# Power.net
KiCad netlist of a schematic drawn in Altium Designer
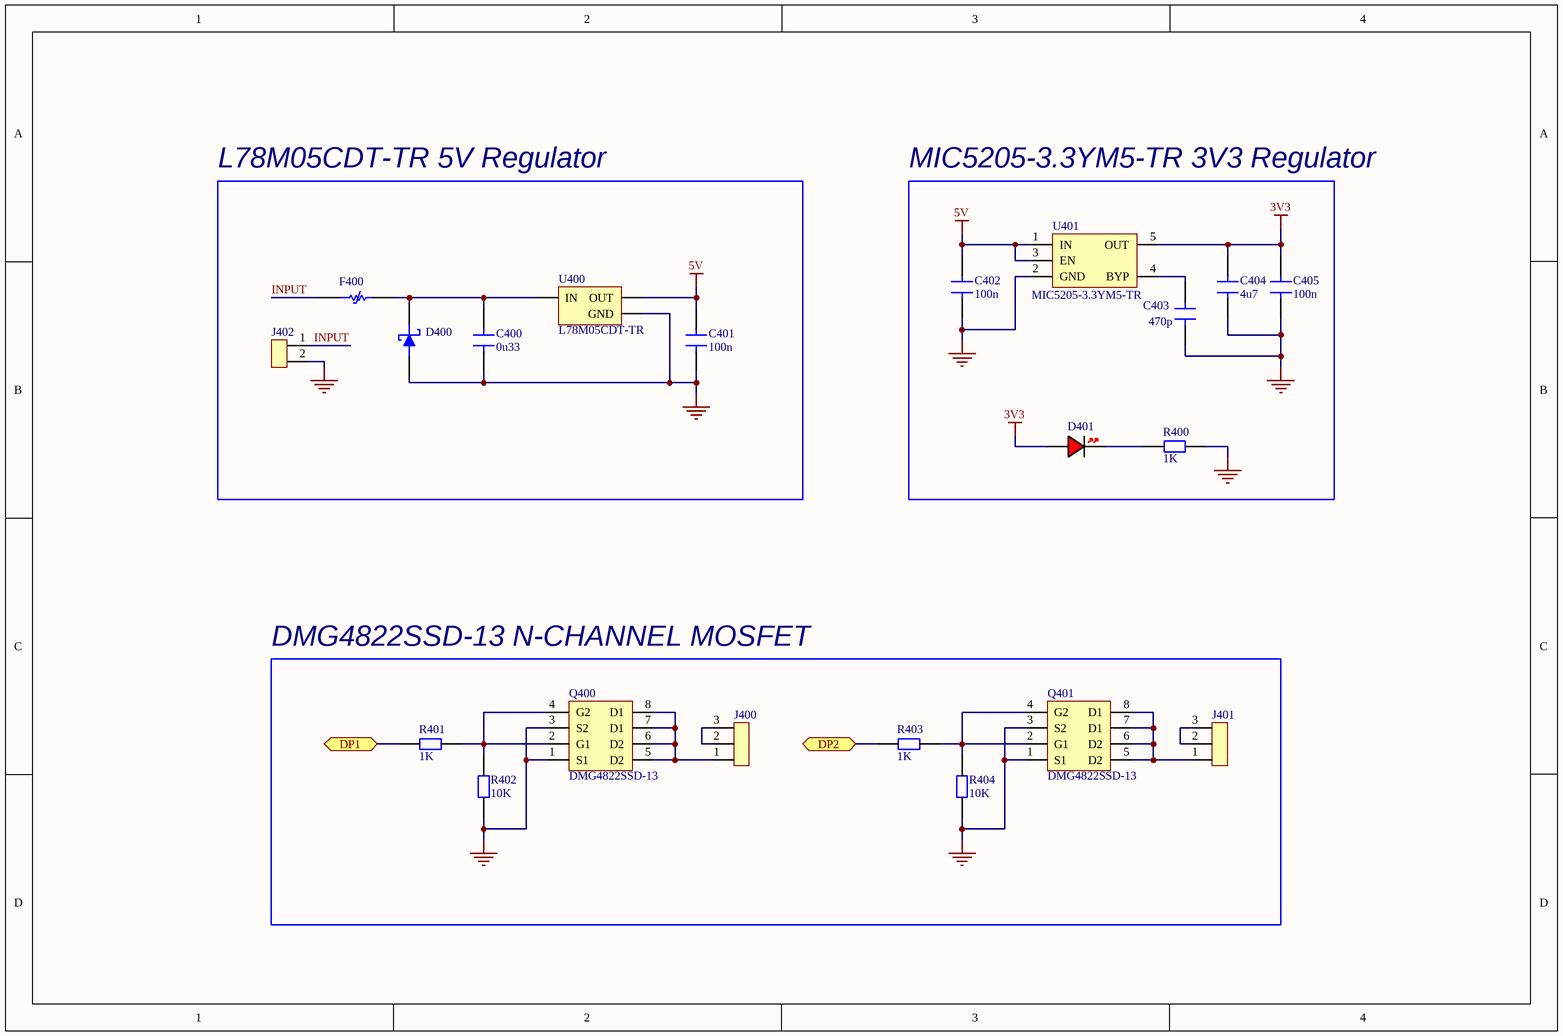
[diagram p0: Power.SchDoc]

(export (version "E")
  (design (tool "Eeschema 10.0.6"))
  (components
    (comp (ref "C400")
      (value "0u33")
      (footprint "CAP 0805")
      (description "Capacitor SMD 0805 50V")
      (libsource (lib "Schlib") (part "CAP 0805 50V"))
    )
    (comp (ref "C401")
      (value "100n")
      (footprint "CAP 0805")
      (description "Capacitor SMD 0805 50V")
      (libsource (lib "Schlib") (part "CAP 0805 50V"))
    )
    (comp (ref "C402")
      (value "100n")
      (footprint "CAP 0805")
      (description "Capacitor SMD 0805 50V")
      (libsource (lib "Schlib") (part "CAP 0805 50V"))
    )
    (comp (ref "C403")
      (value "470p")
      (footprint "CAP 0805")
      (description "Capacitor SMD 0805 50V")
      (libsource (lib "Schlib") (part "CAP 0805 50V"))
    )
    (comp (ref "C404")
      (value "4u7")
      (footprint "CAP 0805")
      (description "Capacitor SMD 0805 50V")
      (libsource (lib "Schlib") (part "CAP 0805 50V"))
    )
    (comp (ref "C405")
      (value "100n")
      (footprint "CAP 0805")
      (description "Capacitor SMD 0805 50V")
      (libsource (lib "Schlib") (part "CAP 0805 50V"))
    )
    (comp (ref "D400")
      (value "SMBJ12CA-13-F")
      (footprint "SMBJ12CA-13-F")
      (description "TVS DIODE 12VWM 19.9VC SMB")
      (fields (field (name "MANUFACTURER") "Diodes"))
      (libsource (lib "Schlib") (part "SMBJ12CA-13-F"))
    )
    (comp (ref "D401")
      (value "LED 0805 RED")
      (footprint "LED 0805 RED")
      (description "LED 0805 RED SMD")
      (libsource (lib "Schlib") (part "LED 0805 RED"))
    )
    (comp (ref "F400")
      (value "0ZCG0075FF2C")
      (footprint "0ZCG0075FF2C")
      (fields (field (name "MANUFACTURER") "Bel"))
      (libsource (lib "Schlib") (part "0ZCG0075FF2C"))
    )
    (comp (ref "J400")
      (value "KF301 3P Terminal")
      (footprint "KF301 3P")
      (description "3 Pin Screw Terminal Block 5mm")
      (libsource (lib "Schlib") (part "KF301 3P Terminal"))
    )
    (comp (ref "J401")
      (value "KF301 3P Terminal")
      (footprint "KF301 3P")
      (description "3 Pin Screw Terminal Block 5mm")
      (libsource (lib "Schlib") (part "KF301 3P Terminal"))
    )
    (comp (ref "J402")
      (value "KF301 2P Terminal")
      (footprint "KF301 2P")
      (description "2 Pin Screw Terminal Block 5mm")
      (libsource (lib "Schlib") (part "KF301 2P Terminal"))
    )
    (comp (ref "Q400")
      (value "DMG4822SSD-13")
      (footprint "DMG4822SSD-13")
      (description "Dual N-Channel 30 V 1.42 W 10.5 nC Enhancement Mode Mosfet - SOIC-8")
      (fields (field (name "MANUFACTURER") "Diodes"))
      (libsource (lib "Schlib") (part "DMG4822SSD-13"))
    )
    (comp (ref "Q401")
      (value "DMG4822SSD-13")
      (footprint "DMG4822SSD-13")
      (description "Dual N-Channel 30 V 1.42 W 10.5 nC Enhancement Mode Mosfet - SOIC-8")
      (fields (field (name "MANUFACTURER") "Diodes"))
      (libsource (lib "Schlib") (part "DMG4822SSD-13"))
    )
    (comp (ref "R400")
      (value "1K")
      (footprint "RES 0603")
      (description "Resistor SMD 0603")
      (libsource (lib "Schlib") (part "RES 0603"))
    )
    (comp (ref "R401")
      (value "1K")
      (footprint "RES 0603")
      (description "Resistor SMD 0603")
      (libsource (lib "Schlib") (part "RES 0603"))
    )
    (comp (ref "R402")
      (value "10K")
      (footprint "RES 0603")
      (description "Resistor SMD 0603")
      (libsource (lib "Schlib") (part "RES 0603"))
    )
    (comp (ref "R403")
      (value "1K")
      (footprint "RES 0603")
      (description "Resistor SMD 0603")
      (libsource (lib "Schlib") (part "RES 0603"))
    )
    (comp (ref "R404")
      (value "10K")
      (footprint "RES 0603")
      (description "Resistor SMD 0603")
      (libsource (lib "Schlib") (part "RES 0603"))
    )
    (comp (ref "U400")
      (value "L78M05CDT-TR")
      (footprint "L78M05CDT-TR")
      (description "IC REG LDO 5V 0.5A DPAK")
      (fields (field (name "MANUFACTURER") "STMicroelectronics") (field (name "TOLERANCE") "5%"))
      (libsource (lib "Schlib") (part "L78M05CDT-TR"))
    )
    (comp (ref "U401")
      (value "MIC5205-3.3YM5-TR")
      (footprint "MIC5205-3.3YM5-TR")
      (description "Linear Voltage Regulator IC Positive Fixed 1 Output 3.3V 150mA SOT-23-5")
      (fields (field (name "MANUFACTURER") "Microchip"))
      (libsource (lib "Schlib") (part "MIC5205-3.3YM5-TR"))
    )
  )
  (nets
    (net (code "1") (name "/DP1") (class "Default")
      (node (ref "R401") (pin "1") (pinfunction "1_1") (pintype "passive"))
    )
    (net (code "2") (name "/DP2") (class "Default")
      (node (ref "R403") (pin "1") (pinfunction "1_1") (pintype "passive"))
    )
    (net (code "3") (name "/INPUT") (class "Default")
      (node (ref "F400") (pin "1") (pintype "passive"))
      (node (ref "J402") (pin "1") (pinfunction "1_1") (pintype "passive"))
    )
    (net (code "4") (name "3V3") (class "Default")
      (node (ref "C404") (pin "2") (pinfunction "2_2") (pintype "passive"))
      (node (ref "C405") (pin "2") (pinfunction "2_2") (pintype "passive"))
      (node (ref "D401") (pin "A") (pinfunction "A_A") (pintype "passive"))
      (node (ref "U401") (pin "5") (pinfunction "OUT_5") (pintype "passive"))
    )
    (net (code "5") (name "5V") (class "Default")
      (node (ref "C401") (pin "2") (pinfunction "2_2") (pintype "passive"))
      (node (ref "C402") (pin "2") (pinfunction "2_2") (pintype "passive"))
      (node (ref "U400") (pin "3") (pinfunction "OUT_3") (pintype "passive"))
      (node (ref "U401") (pin "1") (pinfunction "IN_1") (pintype "passive"))
      (node (ref "U401") (pin "3") (pinfunction "EN_3") (pintype "passive"))
    )
    (net (code "6") (name "GND") (class "Default")
      (node (ref "C400") (pin "1") (pinfunction "1_1") (pintype "passive"))
      (node (ref "C401") (pin "1") (pinfunction "1_1") (pintype "passive"))
      (node (ref "C402") (pin "1") (pinfunction "1_1") (pintype "passive"))
      (node (ref "C403") (pin "1") (pinfunction "1_1") (pintype "passive"))
      (node (ref "C404") (pin "1") (pinfunction "1_1") (pintype "passive"))
      (node (ref "C405") (pin "1") (pinfunction "1_1") (pintype "passive"))
      (node (ref "D400") (pin "1") (pintype "passive"))
      (node (ref "J402") (pin "2") (pinfunction "2_2") (pintype "passive"))
      (node (ref "Q400") (pin "1") (pinfunction "S1_1") (pintype "passive"))
      (node (ref "Q400") (pin "3") (pinfunction "S2_3") (pintype "passive"))
      (node (ref "Q401") (pin "1") (pinfunction "S1_1") (pintype "passive"))
      (node (ref "Q401") (pin "3") (pinfunction "S2_3") (pintype "passive"))
      (node (ref "R400") (pin "2") (pinfunction "2_2") (pintype "passive"))
      (node (ref "R402") (pin "1") (pinfunction "1_1") (pintype "passive"))
      (node (ref "R404") (pin "1") (pinfunction "1_1") (pintype "passive"))
      (node (ref "U400") (pin "2") (pinfunction "GND_2") (pintype "passive"))
      (node (ref "U401") (pin "2") (pinfunction "GND_2") (pintype "passive"))
    )
    (net (code "7") (name "Net-(D401-PadK)") (class "Default")
      (node (ref "D401") (pin "K") (pinfunction "K_K") (pintype "passive"))
      (node (ref "R400") (pin "1") (pinfunction "1_1") (pintype "passive"))
    )
    (net (code "8") (name "Net-(J400-Pad1)") (class "Default")
      (node (ref "J400") (pin "1") (pinfunction "1_1") (pintype "passive"))
      (node (ref "Q400") (pin "5") (pinfunction "D2_5") (pintype "passive"))
      (node (ref "Q400") (pin "6") (pinfunction "D2_6") (pintype "passive"))
      (node (ref "Q400") (pin "7") (pinfunction "D1_7") (pintype "passive"))
      (node (ref "Q400") (pin "8") (pinfunction "D1_8") (pintype "passive"))
    )
    (net (code "9") (name "Net-(J400-Pad2)") (class "Default")
      (node (ref "J400") (pin "2") (pinfunction "2_2") (pintype "passive"))
      (node (ref "J400") (pin "3") (pinfunction "3_3") (pintype "passive"))
    )
    (net (code "10") (name "Net-(J401-Pad1)") (class "Default")
      (node (ref "J401") (pin "1") (pinfunction "1_1") (pintype "passive"))
      (node (ref "Q401") (pin "5") (pinfunction "D2_5") (pintype "passive"))
      (node (ref "Q401") (pin "6") (pinfunction "D2_6") (pintype "passive"))
      (node (ref "Q401") (pin "7") (pinfunction "D1_7") (pintype "passive"))
      (node (ref "Q401") (pin "8") (pinfunction "D1_8") (pintype "passive"))
    )
    (net (code "11") (name "Net-(J401-Pad2)") (class "Default")
      (node (ref "J401") (pin "2") (pinfunction "2_2") (pintype "passive"))
      (node (ref "J401") (pin "3") (pinfunction "3_3") (pintype "passive"))
    )
    (net (code "12") (name "Net-(Q400-G1)") (class "Default")
      (node (ref "Q400") (pin "2") (pinfunction "G1_2") (pintype "passive"))
      (node (ref "Q400") (pin "4") (pinfunction "G2_4") (pintype "passive"))
      (node (ref "R401") (pin "2") (pinfunction "2_2") (pintype "passive"))
      (node (ref "R402") (pin "2") (pinfunction "2_2") (pintype "passive"))
    )
    (net (code "13") (name "Net-(Q401-G1)") (class "Default")
      (node (ref "Q401") (pin "2") (pinfunction "G1_2") (pintype "passive"))
      (node (ref "Q401") (pin "4") (pinfunction "G2_4") (pintype "passive"))
      (node (ref "R403") (pin "2") (pinfunction "2_2") (pintype "passive"))
      (node (ref "R404") (pin "2") (pinfunction "2_2") (pintype "passive"))
    )
    (net (code "14") (name "Net-(U400-IN)") (class "Default")
      (node (ref "C400") (pin "2") (pinfunction "2_2") (pintype "passive"))
      (node (ref "D400") (pin "2") (pintype "passive"))
      (node (ref "F400") (pin "2") (pintype "passive"))
      (node (ref "U400") (pin "1") (pinfunction "IN_1") (pintype "passive"))
    )
    (net (code "15") (name "Net-(U401-BYP)") (class "Default")
      (node (ref "C403") (pin "2") (pinfunction "2_2") (pintype "passive"))
      (node (ref "U401") (pin "4") (pinfunction "BYP_4") (pintype "passive"))
    )
  )
)
